# pcb1f.net
KiCad netlist of a schematic drawn in EAGLE
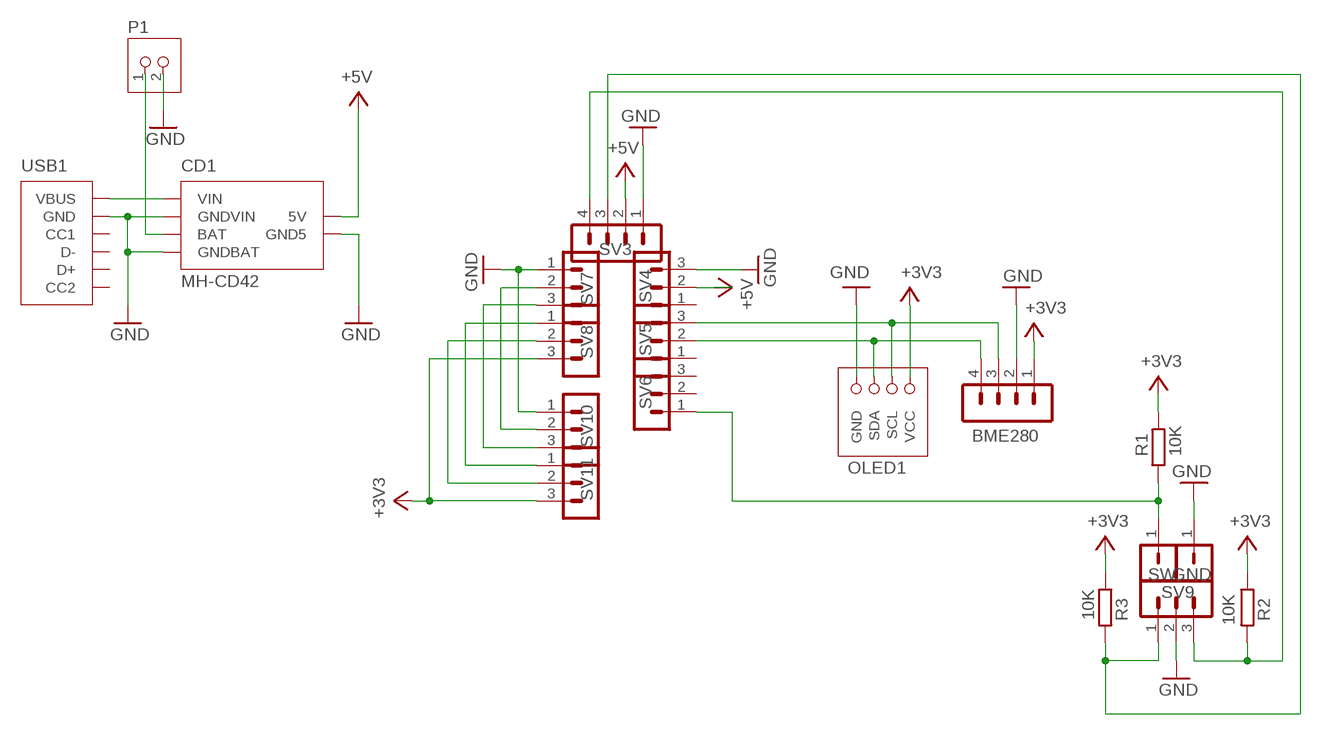
[diagram p0: schematic, sheet 1]

(export (version "E")
  (design (tool "Eeschema 10.0.6"))
  (components
    (comp (ref "BME280")
      (value "PINHEAD-MA04-1")
      (footprint "eagle-import:PINHEAD-MA04-1")
      (libsource (lib "eagle-import") (part "PINHEAD-MA04-1"))
    )
    (comp (ref "CD1")
      (value "MH-CD42")
      (footprint "eagle-import:MH-CD42")
      (libsource (lib "eagle-import") (part "MH-CD42"))
    )
    (comp (ref "GND")
      (value "PINHEAD-MA01-1")
      (footprint "eagle-import:PINHEAD-MA01-1")
      (libsource (lib "eagle-import") (part "PINHEAD-MA01-1"))
    )
    (comp (ref "OLED1")
      (value "OLED-SSD1306-0.96")
      (footprint "eagle-import:OLED-I2C-0.96")
      (libsource (lib "eagle-import") (part "OLED-SSD1306-0.96"))
    )
    (comp (ref "P1")
      (value "JST-PH2")
      (footprint "eagle-import:JST-PH2")
      (libsource (lib "eagle-import") (part "JST-PH2"))
    )
    (comp (ref "R1")
      (value "10K")
      (footprint "eagle-import:0204_5")
      (libsource (lib "eagle-import") (part "R-EU_0204/5"))
    )
    (comp (ref "R2")
      (value "10K")
      (footprint "eagle-import:0204_5")
      (libsource (lib "eagle-import") (part "R-EU_0204/5"))
    )
    (comp (ref "R3")
      (value "10K")
      (footprint "eagle-import:0204_5")
      (libsource (lib "eagle-import") (part "R-EU_0204/5"))
    )
    (comp (ref "SV3")
      (value "PINHEAD-MA04-1")
      (footprint "eagle-import:PINHEAD-MA04-1")
      (libsource (lib "eagle-import") (part "PINHEAD-MA04-1"))
    )
    (comp (ref "SV4")
      (value "PINHEAD-MA03-1")
      (footprint "eagle-import:PINHEAD-MA03-1")
      (libsource (lib "eagle-import") (part "PINHEAD-MA03-1"))
    )
    (comp (ref "SV5")
      (value "PINHEAD-MA03-1")
      (footprint "eagle-import:PINHEAD-MA03-1")
      (libsource (lib "eagle-import") (part "PINHEAD-MA03-1"))
    )
    (comp (ref "SV6")
      (value "PINHEAD-MA03-1")
      (footprint "eagle-import:PINHEAD-MA03-1")
      (libsource (lib "eagle-import") (part "PINHEAD-MA03-1"))
    )
    (comp (ref "SV7")
      (value "PINHEAD-MA03-1")
      (footprint "eagle-import:PINHEAD-MA03-1")
      (libsource (lib "eagle-import") (part "PINHEAD-MA03-1"))
    )
    (comp (ref "SV8")
      (value "PINHEAD-MA03-1")
      (footprint "eagle-import:PINHEAD-MA03-1")
      (libsource (lib "eagle-import") (part "PINHEAD-MA03-1"))
    )
    (comp (ref "SV9")
      (value "PINHEAD-MA03-1")
      (footprint "eagle-import:PINHEAD-MA03-1")
      (libsource (lib "eagle-import") (part "PINHEAD-MA03-1"))
    )
    (comp (ref "SV10")
      (value "PINHEAD-MA03-1")
      (footprint "eagle-import:PINHEAD-MA03-1")
      (libsource (lib "eagle-import") (part "PINHEAD-MA03-1"))
    )
    (comp (ref "SV11")
      (value "PINHEAD-MA03-1")
      (footprint "eagle-import:PINHEAD-MA03-1")
      (libsource (lib "eagle-import") (part "PINHEAD-MA03-1"))
    )
    (comp (ref "SW")
      (value "PINHEAD-MA01-1")
      (footprint "eagle-import:PINHEAD-MA01-1")
      (libsource (lib "eagle-import") (part "PINHEAD-MA01-1"))
    )
    (comp (ref "USB1")
      (value "USB-C-DIRECT")
      (footprint "eagle-import:USB-C-DIRECT")
      (libsource (lib "eagle-import") (part "USB-C-DIRECT"))
    )
  )
  (nets
    (net (code "1") (name "+3V3") (class "Default")
      (node (ref "BME280") (pin "1") (pinfunction "1_1") (pintype "passive"))
      (node (ref "OLED1") (pin "VCC") (pinfunction "VCC_VCC") (pintype "bidirectional"))
      (node (ref "R1") (pin "2") (pinfunction "2_2") (pintype "passive"))
      (node (ref "R2") (pin "1") (pinfunction "1_1") (pintype "passive"))
      (node (ref "R3") (pin "1") (pinfunction "1_1") (pintype "passive"))
      (node (ref "SV11") (pin "3") (pinfunction "3_3") (pintype "passive"))
      (node (ref "SV8") (pin "3") (pinfunction "3_3") (pintype "passive"))
    )
    (net (code "2") (name "+5V") (class "Default")
      (node (ref "CD1") (pin "5V") (pinfunction "5V_5V") (pintype "bidirectional"))
      (node (ref "SV3") (pin "2") (pinfunction "2_2") (pintype "passive"))
      (node (ref "SV4") (pin "2") (pinfunction "2_2") (pintype "passive"))
    )
    (net (code "3") (name "GND") (class "Default")
      (node (ref "BME280") (pin "2") (pinfunction "2_2") (pintype "passive"))
      (node (ref "CD1") (pin "GND5V") (pinfunction "GND5_GND5V") (pintype "bidirectional"))
      (node (ref "CD1") (pin "GNDBAT") (pinfunction "GNDBAT_GNDBAT") (pintype "bidirectional"))
      (node (ref "CD1") (pin "GNDVIN") (pinfunction "GNDVIN_GNDVIN") (pintype "bidirectional"))
      (node (ref "GND") (pin "1") (pinfunction "1_1") (pintype "passive"))
      (node (ref "OLED1") (pin "GND") (pinfunction "GND_GND") (pintype "bidirectional"))
      (node (ref "P1") (pin "2") (pinfunction "2_2") (pintype "passive"))
      (node (ref "SV10") (pin "1") (pinfunction "1_1") (pintype "passive"))
      (node (ref "SV3") (pin "1") (pinfunction "1_1") (pintype "passive"))
      (node (ref "SV4") (pin "3") (pinfunction "3_3") (pintype "passive"))
      (node (ref "SV7") (pin "1") (pinfunction "1_1") (pintype "passive"))
      (node (ref "SV9") (pin "2") (pinfunction "2_2") (pintype "passive"))
      (node (ref "USB1") (pin "GND") (pinfunction "GND_GND") (pintype "bidirectional"))
    )
    (net (code "4") (name "Net-(BME280-Pad3)") (class "Default")
      (node (ref "BME280") (pin "3") (pinfunction "3_3") (pintype "passive"))
      (node (ref "OLED1") (pin "SCL") (pinfunction "SCL_SCL") (pintype "bidirectional"))
      (node (ref "SV5") (pin "3") (pinfunction "3_3") (pintype "passive"))
    )
    (net (code "5") (name "Net-(BME280-Pad4)") (class "Default")
      (node (ref "BME280") (pin "4") (pinfunction "4_4") (pintype "passive"))
      (node (ref "OLED1") (pin "SDA") (pinfunction "SDA_SDA") (pintype "bidirectional"))
      (node (ref "SV5") (pin "2") (pinfunction "2_2") (pintype "passive"))
    )
    (net (code "6") (name "Net-(CD1-PadBAT)") (class "Default")
      (node (ref "CD1") (pin "BAT") (pinfunction "BAT_BAT") (pintype "bidirectional"))
      (node (ref "P1") (pin "1") (pinfunction "1_1") (pintype "passive"))
    )
    (net (code "7") (name "Net-(CD1-PadVIN)") (class "Default")
      (node (ref "CD1") (pin "VIN") (pinfunction "VIN_VIN") (pintype "bidirectional"))
      (node (ref "USB1") (pin "VBUS") (pinfunction "VBUS_VBUS") (pintype "bidirectional"))
    )
    (net (code "8") (name "Net-(R1-Pad1)") (class "Default")
      (node (ref "R1") (pin "1") (pinfunction "1_1") (pintype "passive"))
      (node (ref "SV6") (pin "1") (pinfunction "1_1") (pintype "passive"))
      (node (ref "SW") (pin "1") (pinfunction "1_1") (pintype "passive"))
    )
    (net (code "9") (name "Net-(R2-Pad2)") (class "Default")
      (node (ref "R2") (pin "2") (pinfunction "2_2") (pintype "passive"))
      (node (ref "SV3") (pin "4") (pinfunction "4_4") (pintype "passive"))
      (node (ref "SV9") (pin "3") (pinfunction "3_3") (pintype "passive"))
    )
    (net (code "10") (name "Net-(R3-Pad2)") (class "Default")
      (node (ref "R3") (pin "2") (pinfunction "2_2") (pintype "passive"))
      (node (ref "SV3") (pin "3") (pinfunction "3_3") (pintype "passive"))
      (node (ref "SV9") (pin "1") (pinfunction "1_1") (pintype "passive"))
    )
    (net (code "11") (name "Net-(SV10-Pad2)") (class "Default")
      (node (ref "SV10") (pin "2") (pinfunction "2_2") (pintype "passive"))
      (node (ref "SV7") (pin "2") (pinfunction "2_2") (pintype "passive"))
    )
    (net (code "12") (name "Net-(SV10-Pad3)") (class "Default")
      (node (ref "SV10") (pin "3") (pinfunction "3_3") (pintype "passive"))
      (node (ref "SV7") (pin "3") (pinfunction "3_3") (pintype "passive"))
    )
    (net (code "13") (name "Net-(SV11-Pad1)") (class "Default")
      (node (ref "SV11") (pin "1") (pinfunction "1_1") (pintype "passive"))
      (node (ref "SV8") (pin "1") (pinfunction "1_1") (pintype "passive"))
    )
    (net (code "14") (name "Net-(SV11-Pad2)") (class "Default")
      (node (ref "SV11") (pin "2") (pinfunction "2_2") (pintype "passive"))
      (node (ref "SV8") (pin "2") (pinfunction "2_2") (pintype "passive"))
    )
    (net (code "15") (name "unconnected-(SV4-Pad1)") (class "Default")
      (node (ref "SV4") (pin "1") (pinfunction "1_1") (pintype "passive"))
    )
    (net (code "16") (name "unconnected-(SV5-Pad1)") (class "Default")
      (node (ref "SV5") (pin "1") (pinfunction "1_1") (pintype "passive"))
    )
    (net (code "17") (name "unconnected-(SV6-Pad2)") (class "Default")
      (node (ref "SV6") (pin "2") (pinfunction "2_2") (pintype "passive"))
    )
    (net (code "18") (name "unconnected-(SV6-Pad3)") (class "Default")
      (node (ref "SV6") (pin "3") (pinfunction "3_3") (pintype "passive"))
    )
    (net (code "19") (name "unconnected-(USB1-PadCC1)") (class "Default")
      (node (ref "USB1") (pin "CC1") (pinfunction "CC1_CC1") (pintype "bidirectional"))
    )
    (net (code "20") (name "unconnected-(USB1-PadCC2)") (class "Default")
      (node (ref "USB1") (pin "CC2") (pinfunction "CC2_CC2") (pintype "bidirectional"))
    )
    (net (code "21") (name "unconnected-(USB1-PadD+)") (class "Default")
      (node (ref "USB1") (pin "D+") (pinfunction "D+_D+") (pintype "bidirectional"))
    )
    (net (code "22") (name "unconnected-(USB1-PadD-)") (class "Default")
      (node (ref "USB1") (pin "D-") (pinfunction "D-_D-") (pintype "bidirectional"))
    )
  )
)
